# Sheet1.net
KiCad netlist of a schematic drawn in Altium Designer
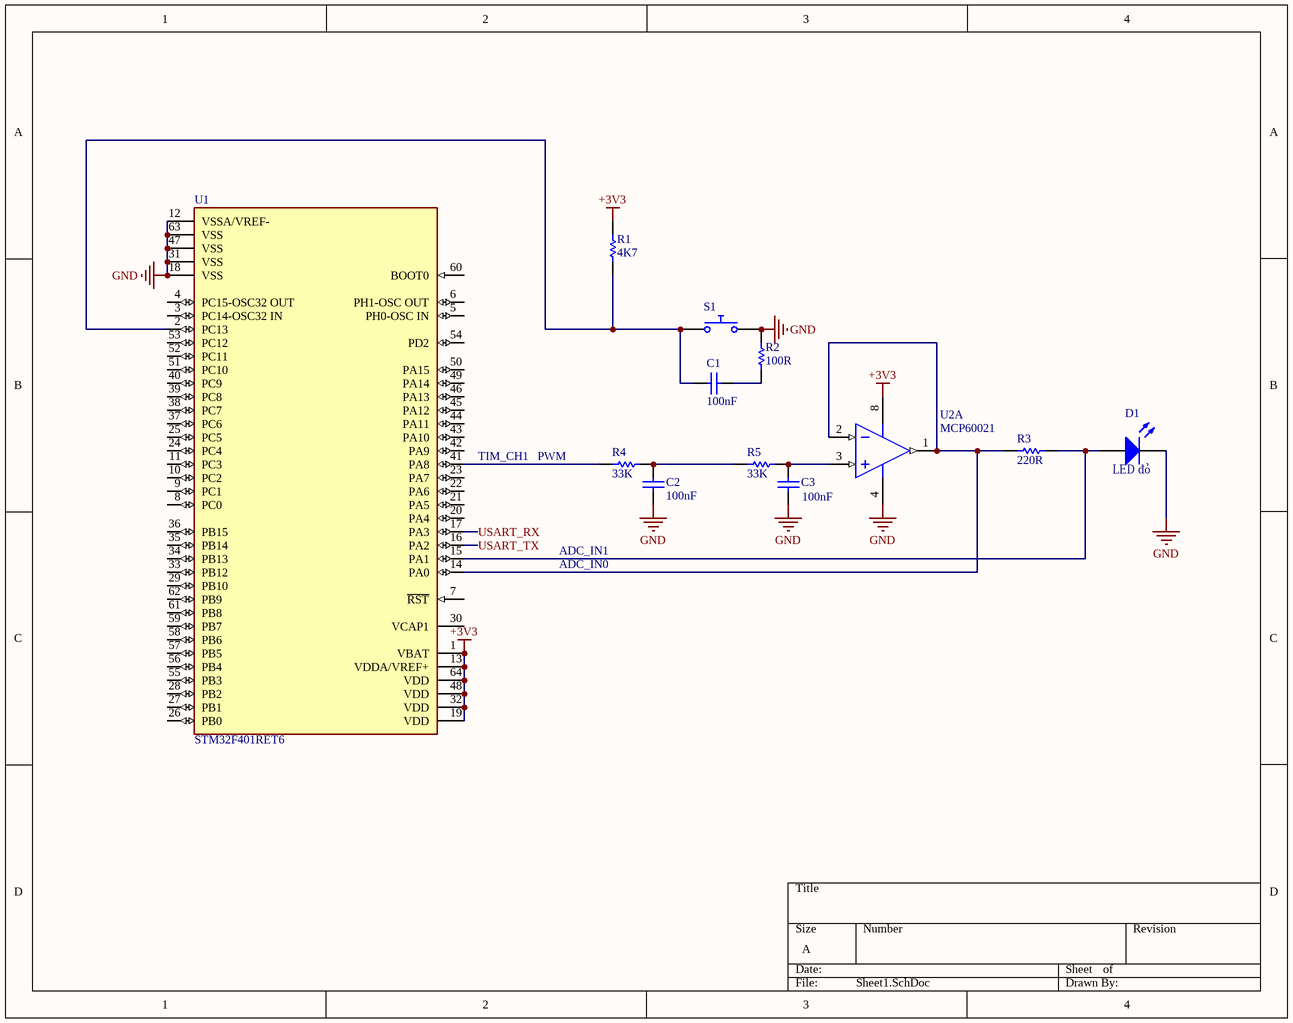
[diagram p0: Sheet1.SchDoc]

(export (version "E")
  (design (tool "Eeschema 10.0.6"))
  (components
    (comp (ref "C1")
      (value "100nF")
      (description "Capacitor")
      (libsource (lib "Simulation Generic Components") (part "Capacitor"))
    )
    (comp (ref "C2")
      (value "100nF")
      (description "Capacitor")
      (libsource (lib "Simulation Generic Components") (part "Capacitor"))
    )
    (comp (ref "C3")
      (value "100nF")
      (description "Capacitor")
      (libsource (lib "Simulation Generic Components") (part "Capacitor"))
    )
    (comp (ref "D1")
      (value "Light-Emitting Diode")
      (libsource (lib "Simulation Generic Components") (part "LED"))
    )
    (comp (ref "R1")
      (value "4K7")
      (description "Resistor")
      (libsource (lib "Simulation Generic Components") (part "Resistor"))
    )
    (comp (ref "R2")
      (value "100R")
      (description "Resistor")
      (libsource (lib "Simulation Generic Components") (part "Resistor"))
    )
    (comp (ref "R3")
      (value "220R")
      (description "Resistor")
      (libsource (lib "Simulation Generic Components") (part "Resistor"))
    )
    (comp (ref "R4")
      (value "33K")
      (description "Resistor")
      (libsource (lib "Simulation Generic Components") (part "Resistor"))
    )
    (comp (ref "R5")
      (value "33K")
      (description "Resistor")
      (libsource (lib "Simulation Generic Components") (part "Resistor"))
    )
    (comp (ref "S1")
      (value "Push Button Normally Opened")
      (libsource (lib "Simulation Generic Components") (part "Push Button NO"))
    )
    (comp (ref "U1")
      (value "STM32F401RET6")
      (footprint "FP-LQFP64-5W-MFG")
      (description "IC MCU 32BIT 512KB FLASH 64LQFP")
      (fields
        (field (name "OCTOPART") "https://octopart.com/stm32f401ret6-stmicroelectronics-34185993")
        (field (name "MANUFACTURER") "STMicroelectronics")
      )
      (libsource (lib "Altium Content Vault") (part "7f49e7cdc56bbeda8d86db7d775c506"))
    )
    (comp (ref "U2")
      (value "MCP60021")
      (footprint "MSOP-MS8_L")
      (description "None")
      (libsource (lib "Altium Content Vault") (part "AMP-OPA-MCP6002-IL8"))
    )
  )
  (nets
    (net (code "1") (name "+3V3") (class "Default")
      (node (ref "R1") (pin "2") (pinfunction "2_2") (pintype "passive"))
      (node (ref "U1") (pin "1") (pinfunction "VBAT_1") (pintype "power_in"))
      (node (ref "U1") (pin "13") (pinfunction "VDDA/VREF+_13") (pintype "power_in"))
      (node (ref "U1") (pin "19") (pinfunction "VDD_19") (pintype "power_in"))
      (node (ref "U1") (pin "32") (pinfunction "VDD_32") (pintype "power_in"))
      (node (ref "U1") (pin "48") (pinfunction "VDD_48") (pintype "power_in"))
      (node (ref "U1") (pin "64") (pinfunction "VDD_64") (pintype "power_in"))
      (node (ref "U2") (pin "8") (pinfunction "VDD_8") (pintype "power_in"))
    )
    (net (code "2") (name "/USART_RX") (class "Default")
      (node (ref "U1") (pin "17") (pinfunction "PA3_17") (pintype "bidirectional"))
    )
    (net (code "3") (name "/USART_TX") (class "Default")
      (node (ref "U1") (pin "16") (pinfunction "PA2_16") (pintype "bidirectional"))
    )
    (net (code "4") (name "GND") (class "Default")
      (node (ref "C2") (pin "1") (pinfunction "1_1") (pintype "passive"))
      (node (ref "C3") (pin "1") (pinfunction "1_1") (pintype "passive"))
      (node (ref "D1") (pin "2") (pinfunction "K_2") (pintype "passive"))
      (node (ref "R2") (pin "2") (pinfunction "2_2") (pintype "passive"))
      (node (ref "S1") (pin "2") (pinfunction "2_2") (pintype "passive"))
      (node (ref "U1") (pin "12") (pinfunction "VSSA/VREF-_12") (pintype "power_in"))
      (node (ref "U1") (pin "18") (pinfunction "VSS_18") (pintype "power_in"))
      (node (ref "U1") (pin "31") (pinfunction "VSS_31") (pintype "power_in"))
      (node (ref "U1") (pin "47") (pinfunction "VSS_47") (pintype "power_in"))
      (node (ref "U1") (pin "63") (pinfunction "VSS_63") (pintype "power_in"))
      (node (ref "U2") (pin "4") (pinfunction "VSS_4") (pintype "power_in"))
    )
    (net (code "5") (name "Net-(C1-Pad1)") (class "Default")
      (node (ref "C1") (pin "1") (pinfunction "1_1") (pintype "passive"))
      (node (ref "R2") (pin "1") (pinfunction "1_1") (pintype "passive"))
    )
    (net (code "6") (name "Net-(C2-Pad2)") (class "Default")
      (node (ref "C2") (pin "2") (pinfunction "2_2") (pintype "passive"))
      (node (ref "R4") (pin "2") (pinfunction "2_2") (pintype "passive"))
      (node (ref "R5") (pin "1") (pinfunction "1_1") (pintype "passive"))
    )
    (net (code "7") (name "Net-(D1-A)") (class "Default")
      (node (ref "D1") (pin "1") (pinfunction "A_1") (pintype "passive"))
      (node (ref "R3") (pin "2") (pinfunction "2_2") (pintype "passive"))
      (node (ref "U1") (pin "15") (pinfunction "PA1_15") (pintype "bidirectional"))
    )
    (net (code "8") (name "Net-(U1-PA0)") (class "Default")
      (node (ref "R3") (pin "1") (pinfunction "1_1") (pintype "passive"))
      (node (ref "U1") (pin "14") (pinfunction "PA0_14") (pintype "bidirectional"))
      (node (ref "U2") (pin "1") (pinfunction "VOUTA_1") (pintype "output"))
      (node (ref "U2") (pin "2") (pinfunction "VINA-_2") (pintype "input"))
    )
    (net (code "9") (name "Net-(U1-PA8)") (class "Default")
      (node (ref "R4") (pin "1") (pinfunction "1_1") (pintype "passive"))
      (node (ref "U1") (pin "41") (pinfunction "PA8_41") (pintype "bidirectional"))
    )
    (net (code "10") (name "Net-(U1-PC13)") (class "Default")
      (node (ref "C1") (pin "2") (pinfunction "2_2") (pintype "passive"))
      (node (ref "R1") (pin "1") (pinfunction "1_1") (pintype "passive"))
      (node (ref "S1") (pin "1") (pinfunction "1_1") (pintype "passive"))
      (node (ref "U1") (pin "2") (pinfunction "PC13_2") (pintype "bidirectional"))
    )
    (net (code "11") (name "Net-(U2A-VINA+)") (class "Default")
      (node (ref "C3") (pin "2") (pinfunction "2_2") (pintype "passive"))
      (node (ref "R5") (pin "2") (pinfunction "2_2") (pintype "passive"))
      (node (ref "U2") (pin "3") (pinfunction "VINA+_3") (pintype "input"))
    )
    (net (code "12") (name "unconnected-(U1-BOOT0-Pad60)") (class "Default")
      (node (ref "U1") (pin "60") (pinfunction "BOOT0_60") (pintype "input"))
    )
    (net (code "13") (name "unconnected-(U1-PA4-Pad20)") (class "Default")
      (node (ref "U1") (pin "20") (pinfunction "PA4_20") (pintype "bidirectional"))
    )
    (net (code "14") (name "unconnected-(U1-PA5-Pad21)") (class "Default")
      (node (ref "U1") (pin "21") (pinfunction "PA5_21") (pintype "bidirectional"))
    )
    (net (code "15") (name "unconnected-(U1-PA6-Pad22)") (class "Default")
      (node (ref "U1") (pin "22") (pinfunction "PA6_22") (pintype "bidirectional"))
    )
    (net (code "16") (name "unconnected-(U1-PA7-Pad23)") (class "Default")
      (node (ref "U1") (pin "23") (pinfunction "PA7_23") (pintype "bidirectional"))
    )
    (net (code "17") (name "unconnected-(U1-PA9-Pad42)") (class "Default")
      (node (ref "U1") (pin "42") (pinfunction "PA9_42") (pintype "bidirectional"))
    )
    (net (code "18") (name "unconnected-(U1-PA10-Pad43)") (class "Default")
      (node (ref "U1") (pin "43") (pinfunction "PA10_43") (pintype "bidirectional"))
    )
    (net (code "19") (name "unconnected-(U1-PA11-Pad44)") (class "Default")
      (node (ref "U1") (pin "44") (pinfunction "PA11_44") (pintype "bidirectional"))
    )
    (net (code "20") (name "unconnected-(U1-PA12-Pad45)") (class "Default")
      (node (ref "U1") (pin "45") (pinfunction "PA12_45") (pintype "bidirectional"))
    )
    (net (code "21") (name "unconnected-(U1-PA13-Pad46)") (class "Default")
      (node (ref "U1") (pin "46") (pinfunction "PA13_46") (pintype "bidirectional"))
    )
    (net (code "22") (name "unconnected-(U1-PA14-Pad49)") (class "Default")
      (node (ref "U1") (pin "49") (pinfunction "PA14_49") (pintype "bidirectional"))
    )
    (net (code "23") (name "unconnected-(U1-PA15-Pad50)") (class "Default")
      (node (ref "U1") (pin "50") (pinfunction "PA15_50") (pintype "bidirectional"))
    )
    (net (code "24") (name "unconnected-(U1-PB0-Pad26)") (class "Default")
      (node (ref "U1") (pin "26") (pinfunction "PB0_26") (pintype "bidirectional"))
    )
    (net (code "25") (name "unconnected-(U1-PB1-Pad27)") (class "Default")
      (node (ref "U1") (pin "27") (pinfunction "PB1_27") (pintype "bidirectional"))
    )
    (net (code "26") (name "unconnected-(U1-PB2-Pad28)") (class "Default")
      (node (ref "U1") (pin "28") (pinfunction "PB2_28") (pintype "bidirectional"))
    )
    (net (code "27") (name "unconnected-(U1-PB3-Pad55)") (class "Default")
      (node (ref "U1") (pin "55") (pinfunction "PB3_55") (pintype "bidirectional"))
    )
    (net (code "28") (name "unconnected-(U1-PB4-Pad56)") (class "Default")
      (node (ref "U1") (pin "56") (pinfunction "PB4_56") (pintype "bidirectional"))
    )
    (net (code "29") (name "unconnected-(U1-PB5-Pad57)") (class "Default")
      (node (ref "U1") (pin "57") (pinfunction "PB5_57") (pintype "bidirectional"))
    )
    (net (code "30") (name "unconnected-(U1-PB6-Pad58)") (class "Default")
      (node (ref "U1") (pin "58") (pinfunction "PB6_58") (pintype "bidirectional"))
    )
    (net (code "31") (name "unconnected-(U1-PB7-Pad59)") (class "Default")
      (node (ref "U1") (pin "59") (pinfunction "PB7_59") (pintype "bidirectional"))
    )
    (net (code "32") (name "unconnected-(U1-PB8-Pad61)") (class "Default")
      (node (ref "U1") (pin "61") (pinfunction "PB8_61") (pintype "bidirectional"))
    )
    (net (code "33") (name "unconnected-(U1-PB9-Pad62)") (class "Default")
      (node (ref "U1") (pin "62") (pinfunction "PB9_62") (pintype "bidirectional"))
    )
    (net (code "34") (name "unconnected-(U1-PB10-Pad29)") (class "Default")
      (node (ref "U1") (pin "29") (pinfunction "PB10_29") (pintype "bidirectional"))
    )
    (net (code "35") (name "unconnected-(U1-PB12-Pad33)") (class "Default")
      (node (ref "U1") (pin "33") (pinfunction "PB12_33") (pintype "bidirectional"))
    )
    (net (code "36") (name "unconnected-(U1-PB13-Pad34)") (class "Default")
      (node (ref "U1") (pin "34") (pinfunction "PB13_34") (pintype "bidirectional"))
    )
    (net (code "37") (name "unconnected-(U1-PB14-Pad35)") (class "Default")
      (node (ref "U1") (pin "35") (pinfunction "PB14_35") (pintype "bidirectional"))
    )
    (net (code "38") (name "unconnected-(U1-PB15-Pad36)") (class "Default")
      (node (ref "U1") (pin "36") (pinfunction "PB15_36") (pintype "bidirectional"))
    )
    (net (code "39") (name "unconnected-(U1-PC0-Pad8)") (class "Default")
      (node (ref "U1") (pin "8") (pinfunction "PC0_8") (pintype "bidirectional"))
    )
    (net (code "40") (name "unconnected-(U1-PC1-Pad9)") (class "Default")
      (node (ref "U1") (pin "9") (pinfunction "PC1_9") (pintype "bidirectional"))
    )
    (net (code "41") (name "unconnected-(U1-PC2-Pad10)") (class "Default")
      (node (ref "U1") (pin "10") (pinfunction "PC2_10") (pintype "bidirectional"))
    )
    (net (code "42") (name "unconnected-(U1-PC3-Pad11)") (class "Default")
      (node (ref "U1") (pin "11") (pinfunction "PC3_11") (pintype "bidirectional"))
    )
    (net (code "43") (name "unconnected-(U1-PC4-Pad24)") (class "Default")
      (node (ref "U1") (pin "24") (pinfunction "PC4_24") (pintype "bidirectional"))
    )
    (net (code "44") (name "unconnected-(U1-PC5-Pad25)") (class "Default")
      (node (ref "U1") (pin "25") (pinfunction "PC5_25") (pintype "bidirectional"))
    )
    (net (code "45") (name "unconnected-(U1-PC6-Pad37)") (class "Default")
      (node (ref "U1") (pin "37") (pinfunction "PC6_37") (pintype "bidirectional"))
    )
    (net (code "46") (name "unconnected-(U1-PC7-Pad38)") (class "Default")
      (node (ref "U1") (pin "38") (pinfunction "PC7_38") (pintype "bidirectional"))
    )
    (net (code "47") (name "unconnected-(U1-PC8-Pad39)") (class "Default")
      (node (ref "U1") (pin "39") (pinfunction "PC8_39") (pintype "bidirectional"))
    )
    (net (code "48") (name "unconnected-(U1-PC9-Pad40)") (class "Default")
      (node (ref "U1") (pin "40") (pinfunction "PC9_40") (pintype "bidirectional"))
    )
    (net (code "49") (name "unconnected-(U1-PC10-Pad51)") (class "Default")
      (node (ref "U1") (pin "51") (pinfunction "PC10_51") (pintype "bidirectional"))
    )
    (net (code "50") (name "unconnected-(U1-PC11-Pad52)") (class "Default")
      (node (ref "U1") (pin "52") (pinfunction "PC11_52") (pintype "bidirectional"))
    )
    (net (code "51") (name "unconnected-(U1-PC12-Pad53)") (class "Default")
      (node (ref "U1") (pin "53") (pinfunction "PC12_53") (pintype "bidirectional"))
    )
    (net (code "52") (name "unconnected-(U1-PC14-OSC32_IN-Pad3)") (class "Default")
      (node (ref "U1") (pin "3") (pinfunction "PC14-OSC32_IN_3") (pintype "bidirectional"))
    )
    (net (code "53") (name "unconnected-(U1-PC15-OSC32_OUT-Pad4)") (class "Default")
      (node (ref "U1") (pin "4") (pinfunction "PC15-OSC32_OUT_4") (pintype "bidirectional"))
    )
    (net (code "54") (name "unconnected-(U1-PD2-Pad54)") (class "Default")
      (node (ref "U1") (pin "54") (pinfunction "PD2_54") (pintype "bidirectional"))
    )
    (net (code "55") (name "unconnected-(U1-PH0-OSC_IN-Pad5)") (class "Default")
      (node (ref "U1") (pin "5") (pinfunction "PH0-OSC_IN_5") (pintype "bidirectional"))
    )
    (net (code "56") (name "unconnected-(U1-PH1-OSC_OUT-Pad6)") (class "Default")
      (node (ref "U1") (pin "6") (pinfunction "PH1-OSC_OUT_6") (pintype "bidirectional"))
    )
    (net (code "57") (name "unconnected-(U1-VCAP1-Pad30)") (class "Default")
      (node (ref "U1") (pin "30") (pinfunction "VCAP1_30") (pintype "power_in"))
    )
    (net (code "58") (name "unconnected-(U1-~{RST}-Pad7)") (class "Default")
      (node (ref "U1") (pin "7") (pinfunction "~{RST}_7") (pintype "input"))
    )
  )
)
